# SDRAM_2.net
KiCad netlist of a schematic drawn in Altium Designer
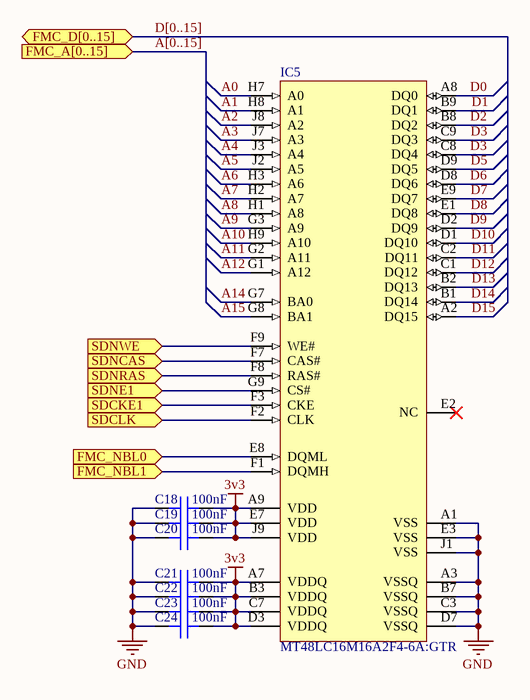
[diagram p0: SDRAM 2.SchDoc]

(export (version "E")
  (design (tool "Eeschema 10.0.6"))
  (components
    (comp (ref "C18")
      (value "100nF")
      (footprint "CAP 0603/1608")
      (description "Ceramic, SMT Capacitor")
      (fields
        (field (name "MANUFACTURER") "Samsung")
        (field (name "MANUFACTURER PART NUMBER") "CL10B104JB8NNNC")
      )
      (libsource (lib "yildizIoT Library") (part "Capacitor - Ceramic"))
    )
    (comp (ref "C19")
      (value "100nF")
      (footprint "CAP 0603/1608")
      (description "Ceramic, SMT Capacitor")
      (fields
        (field (name "MANUFACTURER") "Samsung")
        (field (name "MANUFACTURER PART NUMBER") "CL10B104JB8NNNC")
      )
      (libsource (lib "yildizIoT Library") (part "Capacitor - Ceramic"))
    )
    (comp (ref "C20")
      (value "100nF")
      (footprint "CAP 0603/1608")
      (description "Ceramic, SMT Capacitor")
      (fields
        (field (name "MANUFACTURER") "Samsung")
        (field (name "MANUFACTURER PART NUMBER") "CL10B104JB8NNNC")
      )
      (libsource (lib "yildizIoT Library") (part "Capacitor - Ceramic"))
    )
    (comp (ref "C21")
      (value "100nF")
      (footprint "CAP 0603/1608")
      (description "Ceramic, SMT Capacitor")
      (fields
        (field (name "MANUFACTURER") "Samsung")
        (field (name "MANUFACTURER PART NUMBER") "CL10B104JB8NNNC")
      )
      (libsource (lib "yildizIoT Library") (part "Capacitor - Ceramic"))
    )
    (comp (ref "C22")
      (value "100nF")
      (footprint "CAP 0603/1608")
      (description "Ceramic, SMT Capacitor")
      (fields
        (field (name "MANUFACTURER") "Samsung")
        (field (name "MANUFACTURER PART NUMBER") "CL10B104JB8NNNC")
      )
      (libsource (lib "yildizIoT Library") (part "Capacitor - Ceramic"))
    )
    (comp (ref "C23")
      (value "100nF")
      (footprint "CAP 0603/1608")
      (description "Ceramic, SMT Capacitor")
      (fields
        (field (name "MANUFACTURER") "Samsung")
        (field (name "MANUFACTURER PART NUMBER") "CL10B104JB8NNNC")
      )
      (libsource (lib "yildizIoT Library") (part "Capacitor - Ceramic"))
    )
    (comp (ref "C24")
      (value "100nF")
      (footprint "CAP 0603/1608")
      (description "Ceramic, SMT Capacitor")
      (fields
        (field (name "MANUFACTURER") "Samsung")
        (field (name "MANUFACTURER PART NUMBER") "CL10B104JB8NNNC")
      )
      (libsource (lib "yildizIoT Library") (part "Capacitor - Ceramic"))
    )
    (comp (ref "IC5")
      (value "MT48LC16M16A2F4-6A:GTR")
      (footprint "MICRON VFBGA-54 8X14MM")
      (fields (field (name "MANUFACTURER") "Alliance Memory"))
      (libsource (lib "yildizIoT Library") (part "MICRON 256Mb SDRAM"))
    )
  )
  (nets
    (net (code "3") (name "/A0") (class "Default")
      (node (ref "IC5") (pin "H7") (pinfunction "A0_H7") (pintype "input"))
    )
    (net (code "4") (name "/A1") (class "Default")
      (node (ref "IC5") (pin "H8") (pinfunction "A1_H8") (pintype "input"))
    )
    (net (code "5") (name "/A2") (class "Default")
      (node (ref "IC5") (pin "J8") (pinfunction "A2_J8") (pintype "input"))
    )
    (net (code "6") (name "/A3") (class "Default")
      (node (ref "IC5") (pin "J7") (pinfunction "A3_J7") (pintype "input"))
    )
    (net (code "7") (name "/A4") (class "Default")
      (node (ref "IC5") (pin "J3") (pinfunction "A4_J3") (pintype "input"))
    )
    (net (code "8") (name "/A5") (class "Default")
      (node (ref "IC5") (pin "J2") (pinfunction "A5_J2") (pintype "input"))
    )
    (net (code "9") (name "/A6") (class "Default")
      (node (ref "IC5") (pin "H3") (pinfunction "A6_H3") (pintype "input"))
    )
    (net (code "10") (name "/A7") (class "Default")
      (node (ref "IC5") (pin "H2") (pinfunction "A7_H2") (pintype "input"))
    )
    (net (code "11") (name "/A8") (class "Default")
      (node (ref "IC5") (pin "H1") (pinfunction "A8_H1") (pintype "input"))
    )
    (net (code "12") (name "/A9") (class "Default")
      (node (ref "IC5") (pin "G3") (pinfunction "A9_G3") (pintype "input"))
    )
    (net (code "13") (name "/A10") (class "Default")
      (node (ref "IC5") (pin "H9") (pinfunction "A10_H9") (pintype "input"))
    )
    (net (code "14") (name "/A11") (class "Default")
      (node (ref "IC5") (pin "G2") (pinfunction "A11_G2") (pintype "input"))
    )
    (net (code "15") (name "/A12") (class "Default")
      (node (ref "IC5") (pin "G1") (pinfunction "A12_G1") (pintype "input"))
    )
    (net (code "16") (name "/A14") (class "Default")
      (node (ref "IC5") (pin "G7") (pinfunction "BA0_G7") (pintype "input"))
    )
    (net (code "17") (name "/A15") (class "Default")
      (node (ref "IC5") (pin "G8") (pinfunction "BA1_G8") (pintype "input"))
    )
    (net (code "19") (name "/D0") (class "Default")
      (node (ref "IC5") (pin "A8") (pinfunction "DQ0_A8") (pintype "bidirectional"))
    )
    (net (code "20") (name "/D1") (class "Default")
      (node (ref "IC5") (pin "B9") (pinfunction "DQ1_B9") (pintype "bidirectional"))
    )
    (net (code "21") (name "/D2") (class "Default")
      (node (ref "IC5") (pin "B8") (pinfunction "DQ2_B8") (pintype "bidirectional"))
    )
    (net (code "22") (name "/D3") (class "Default")
      (node (ref "IC5") (pin "C8") (pinfunction "DQ4_C8") (pintype "bidirectional"))
      (node (ref "IC5") (pin "C9") (pinfunction "DQ3_C9") (pintype "bidirectional"))
    )
    (net (code "23") (name "/D5") (class "Default")
      (node (ref "IC5") (pin "D9") (pinfunction "DQ5_D9") (pintype "bidirectional"))
    )
    (net (code "24") (name "/D6") (class "Default")
      (node (ref "IC5") (pin "D8") (pinfunction "DQ6_D8") (pintype "bidirectional"))
    )
    (net (code "25") (name "/D7") (class "Default")
      (node (ref "IC5") (pin "E9") (pinfunction "DQ7_E9") (pintype "bidirectional"))
    )
    (net (code "26") (name "/D8") (class "Default")
      (node (ref "IC5") (pin "E1") (pinfunction "DQ8_E1") (pintype "bidirectional"))
    )
    (net (code "27") (name "/D9") (class "Default")
      (node (ref "IC5") (pin "D2") (pinfunction "DQ9_D2") (pintype "bidirectional"))
    )
    (net (code "28") (name "/D10") (class "Default")
      (node (ref "IC5") (pin "D1") (pinfunction "DQ10_D1") (pintype "bidirectional"))
    )
    (net (code "29") (name "/D11") (class "Default")
      (node (ref "IC5") (pin "C2") (pinfunction "DQ11_C2") (pintype "bidirectional"))
    )
    (net (code "30") (name "/D12") (class "Default")
      (node (ref "IC5") (pin "C1") (pinfunction "DQ12_C1") (pintype "bidirectional"))
    )
    (net (code "31") (name "/D13") (class "Default")
      (node (ref "IC5") (pin "B2") (pinfunction "DQ13_B2") (pintype "bidirectional"))
    )
    (net (code "32") (name "/D14") (class "Default")
      (node (ref "IC5") (pin "B1") (pinfunction "DQ14_B1") (pintype "bidirectional"))
    )
    (net (code "33") (name "/D15") (class "Default")
      (node (ref "IC5") (pin "A2") (pinfunction "DQ15_A2") (pintype "bidirectional"))
    )
    (net (code "35") (name "/FMC_NBL0") (class "Default")
      (node (ref "IC5") (pin "E8") (pinfunction "DQML_E8") (pintype "input"))
    )
    (net (code "36") (name "/FMC_NBL1") (class "Default")
      (node (ref "IC5") (pin "F1") (pinfunction "DQMH_F1") (pintype "input"))
    )
    (net (code "37") (name "/SDCKE1") (class "Default")
      (node (ref "IC5") (pin "F3") (pinfunction "CKE_F3") (pintype "input"))
    )
    (net (code "38") (name "/SDCLK") (class "Default")
      (node (ref "IC5") (pin "F2") (pinfunction "CLK_F2") (pintype "input"))
    )
    (net (code "39") (name "/SDNCAS") (class "Default")
      (node (ref "IC5") (pin "F7") (pinfunction "CAS#_F7") (pintype "input"))
    )
    (net (code "40") (name "/SDNE1") (class "Default")
      (node (ref "IC5") (pin "G9") (pinfunction "CS#_G9") (pintype "input"))
    )
    (net (code "41") (name "/SDNRAS") (class "Default")
      (node (ref "IC5") (pin "F8") (pinfunction "RAS#_F8") (pintype "input"))
    )
    (net (code "42") (name "/SDNWE") (class "Default")
      (node (ref "IC5") (pin "F9") (pinfunction "WE#_F9") (pintype "input"))
    )
    (net (code "43") (name "3v3") (class "Default")
      (node (ref "C18") (pin "1") (pinfunction "1_1") (pintype "passive"))
      (node (ref "C19") (pin "1") (pinfunction "1_1") (pintype "passive"))
      (node (ref "C20") (pin "1") (pinfunction "1_1") (pintype "passive"))
      (node (ref "C21") (pin "1") (pinfunction "1_1") (pintype "passive"))
      (node (ref "C22") (pin "1") (pinfunction "1_1") (pintype "passive"))
      (node (ref "C23") (pin "1") (pinfunction "1_1") (pintype "passive"))
      (node (ref "C24") (pin "1") (pinfunction "1_1") (pintype "passive"))
      (node (ref "IC5") (pin "A7") (pinfunction "VDDQ_A7") (pintype "power_in"))
      (node (ref "IC5") (pin "A9") (pinfunction "VDD_A9") (pintype "power_in"))
      (node (ref "IC5") (pin "B3") (pinfunction "VDDQ_B3") (pintype "power_in"))
      (node (ref "IC5") (pin "C7") (pinfunction "VDDQ_C7") (pintype "power_in"))
      (node (ref "IC5") (pin "D3") (pinfunction "VDDQ_D3") (pintype "power_in"))
      (node (ref "IC5") (pin "E7") (pinfunction "VDD_E7") (pintype "power_in"))
      (node (ref "IC5") (pin "J9") (pinfunction "VDD_J9") (pintype "power_in"))
    )
    (net (code "44") (name "GND") (class "Default")
      (node (ref "C18") (pin "2") (pinfunction "2_2") (pintype "passive"))
      (node (ref "C19") (pin "2") (pinfunction "2_2") (pintype "passive"))
      (node (ref "C20") (pin "2") (pinfunction "2_2") (pintype "passive"))
      (node (ref "C21") (pin "2") (pinfunction "2_2") (pintype "passive"))
      (node (ref "C22") (pin "2") (pinfunction "2_2") (pintype "passive"))
      (node (ref "C23") (pin "2") (pinfunction "2_2") (pintype "passive"))
      (node (ref "C24") (pin "2") (pinfunction "2_2") (pintype "passive"))
      (node (ref "IC5") (pin "A1") (pinfunction "VSS_A1") (pintype "power_in"))
      (node (ref "IC5") (pin "A3") (pinfunction "VSSQ_A3") (pintype "power_in"))
      (node (ref "IC5") (pin "B7") (pinfunction "VSSQ_B7") (pintype "power_in"))
      (node (ref "IC5") (pin "C3") (pinfunction "VSSQ_C3") (pintype "power_in"))
      (node (ref "IC5") (pin "D7") (pinfunction "VSSQ_D7") (pintype "power_in"))
      (node (ref "IC5") (pin "E3") (pinfunction "VSS_E3") (pintype "power_in"))
      (node (ref "IC5") (pin "J1") (pinfunction "VSS_J1") (pintype "power_in"))
    )
    (net (code "45") (name "unconnected-(IC5-NC-PadE2)") (class "Default")
      (node (ref "IC5") (pin "E2") (pinfunction "NC_E2") (pintype "passive+no_connect"))
    )
  )
)
